# Executive_12V_C.net
KiCad netlist of a schematic drawn in EAGLE
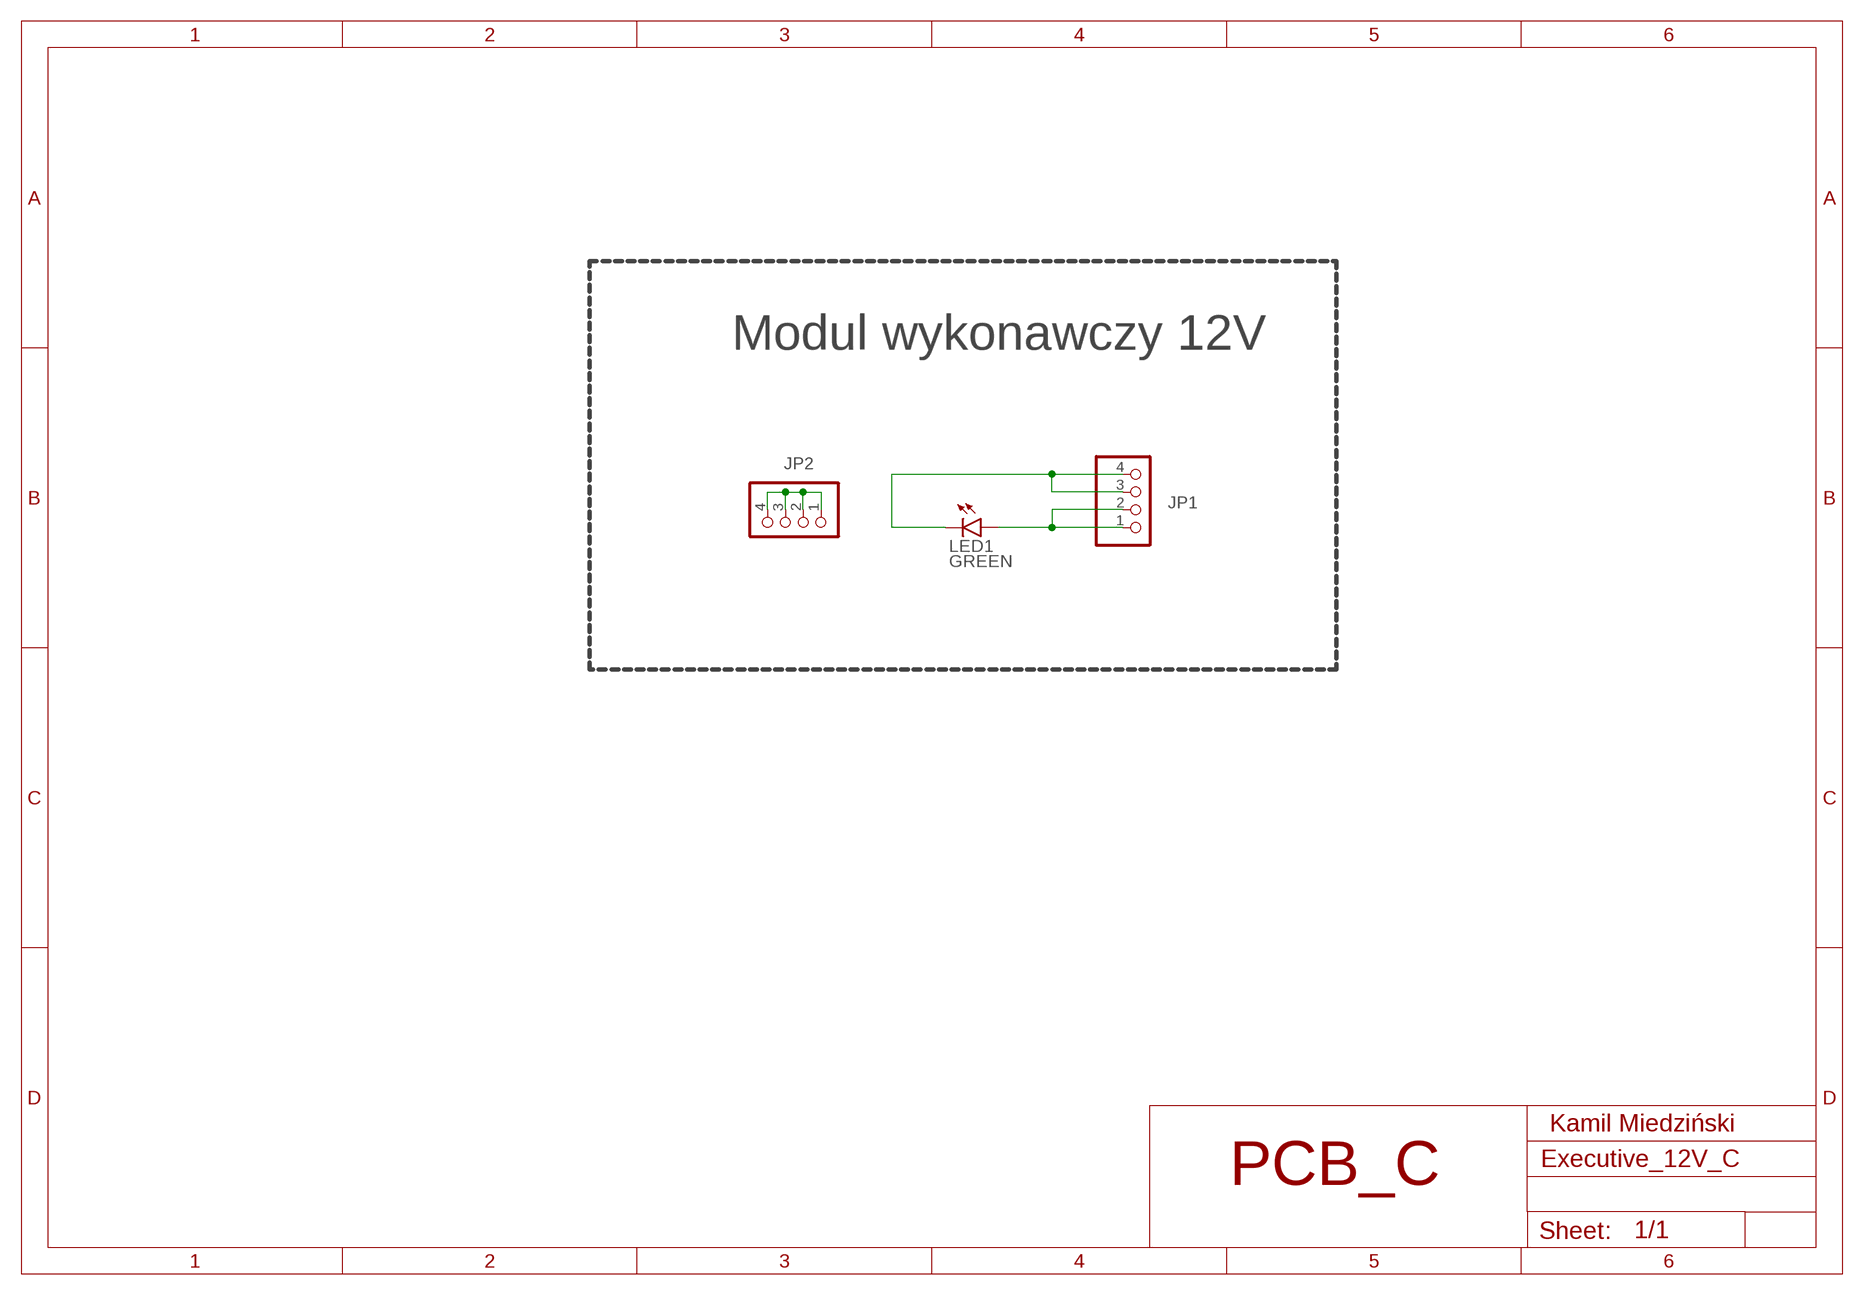
[diagram p0: schematic, sheet 1]

(export (version "E")
  (design (tool "Eeschema 10.0.6"))
  (components
    (comp (ref "JP1")
      (value "PINHD-1X41X04H")
      (footprint "eagle-import:1X04H")
      (libsource (lib "eagle-import") (part "PINHD-1X41X04H"))
    )
    (comp (ref "JP2")
      (value "PINHD-1X41X04H")
      (footprint "eagle-import:1X04H")
      (libsource (lib "eagle-import") (part "PINHD-1X41X04H"))
    )
    (comp (ref "LED1")
      (value "GREEN")
      (footprint "eagle-import:LED5MM_GREEN")
      (libsource (lib "eagle-import") (part "LED5MM_GREEN"))
    )
  )
  (nets
    (net (code "1") (name "Net-(JP1-Pad1)") (class "Default")
      (node (ref "JP1") (pin "1") (pinfunction "1_1") (pintype "passive"))
      (node (ref "JP1") (pin "2") (pinfunction "2_2") (pintype "passive"))
      (node (ref "LED1") (pin "A") (pinfunction "A_A") (pintype "passive"))
    )
    (net (code "2") (name "Net-(JP2-Pad1)") (class "Default")
      (node (ref "JP2") (pin "1") (pinfunction "1_1") (pintype "passive"))
      (node (ref "JP2") (pin "2") (pinfunction "2_2") (pintype "passive"))
      (node (ref "JP2") (pin "3") (pinfunction "3_3") (pintype "passive"))
      (node (ref "JP2") (pin "4") (pinfunction "4_4") (pintype "passive"))
    )
    (net (code "3") (name "Net-(LED1-C)") (class "Default")
      (node (ref "JP1") (pin "3") (pinfunction "3_3") (pintype "passive"))
      (node (ref "JP1") (pin "4") (pinfunction "4_4") (pintype "passive"))
      (node (ref "LED1") (pin "K") (pinfunction "C_K") (pintype "passive"))
    )
  )
)
